# LTC3862-2.net
KiCad netlist of a schematic drawn in Altium Designer
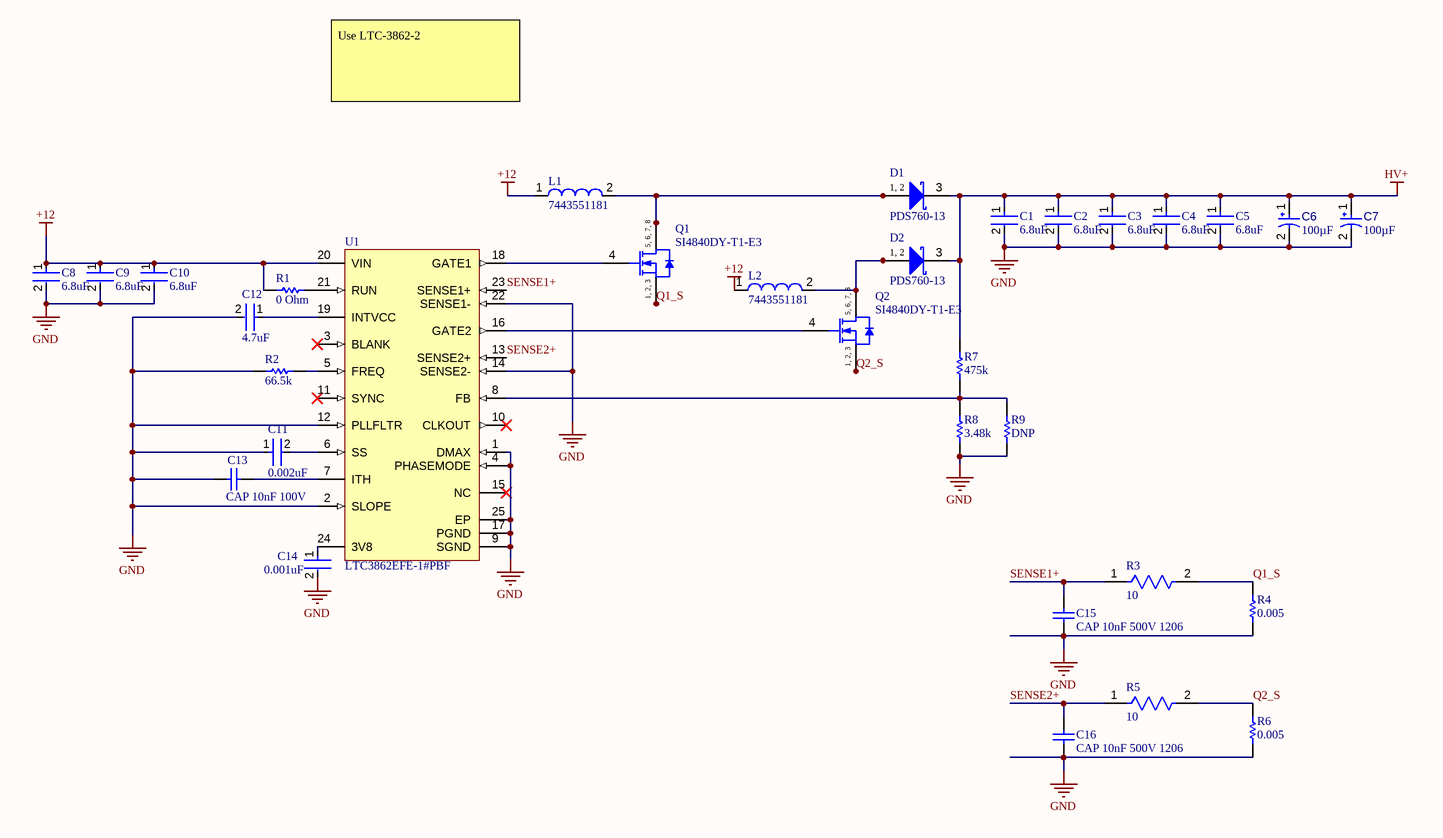
[diagram p0: LTC3862-2.SchDoc]

(export (version "E")
  (design (tool "Eeschema 10.0.6"))
  (components
    (comp (ref "C1")
      (value "6.8uF")
      (footprint "FP-C3216-160-0_2-MFG")
      (description "Multilayer Ceramic Capacitors 6.8uF ±20% 50V X5R SMD 1206\r\nC3216X5R1H685M160AB")
      (fields (field (name "TOLERANCE") "20%"))
      (libsource (lib "Altium Content Vault") (part "11868f565c42a9108669ba33697ecf6"))
    )
    (comp (ref "C2")
      (value "6.8uF")
      (footprint "FP-C3216-160-0_2-MFG")
      (description "Multilayer Ceramic Capacitors 6.8uF ±20% 50V X5R SMD 1206\r\nC3216X5R1H685M160AB")
      (fields (field (name "TOLERANCE") "20%"))
      (libsource (lib "Altium Content Vault") (part "11868f565c42a9108669ba33697ecf6"))
    )
    (comp (ref "C3")
      (value "6.8uF")
      (footprint "FP-C3216-160-0_2-MFG")
      (description "Multilayer Ceramic Capacitors 6.8uF ±20% 50V X5R SMD 1206\r\nC3216X5R1H685M160AB")
      (fields (field (name "TOLERANCE") "20%"))
      (libsource (lib "Altium Content Vault") (part "11868f565c42a9108669ba33697ecf6"))
    )
    (comp (ref "C4")
      (value "6.8uF")
      (footprint "FP-C3216-160-0_2-MFG")
      (description "Multilayer Ceramic Capacitors 6.8uF ±20% 50V X5R SMD 1206\r\nC3216X5R1H685M160AB")
      (fields (field (name "TOLERANCE") "20%"))
      (libsource (lib "Altium Content Vault") (part "11868f565c42a9108669ba33697ecf6"))
    )
    (comp (ref "C5")
      (value "6.8uF")
      (footprint "FP-C3216-160-0_2-MFG")
      (description "Multilayer Ceramic Capacitors 6.8uF ±20% 50V X5R SMD 1206\r\nC3216X5R1H685M160AB")
      (fields (field (name "TOLERANCE") "20%"))
      (libsource (lib "Altium Content Vault") (part "11868f565c42a9108669ba33697ecf6"))
    )
    (comp (ref "C6")
      (value "100µF")
      (footprint "CAPPR65-500-1600X1000X1700")
      (description "Aluminum Electrolytic Capacitor, 100 uF, +/- 20%, 200 V, -40 to 85 degC, 2-Pin THD, RoHS, Bulk")
      (fields (field (name "MANUFACTURER") "Panasonic") (field (name "TOLERANCE") "20%"))
      (libsource (lib "University of California Riverside - FSAE") (part "CAP-P-2"))
    )
    (comp (ref "C7")
      (value "100µF")
      (footprint "CAPPR65-500-1600X1000X1700")
      (description "Aluminum Electrolytic Capacitor, 100 uF, +/- 20%, 200 V, -40 to 85 degC, 2-Pin THD, RoHS, Bulk")
      (fields (field (name "MANUFACTURER") "Panasonic") (field (name "TOLERANCE") "20%"))
      (libsource (lib "University of California Riverside - FSAE") (part "CAP-P-2"))
    )
    (comp (ref "C8")
      (value "6.8uF")
      (footprint "FP-C3216-160-0_2-IPC_B")
      (description "Multilayer Ceramic Capacitors 6.8uF ±10% 25V X7R SMD 1206\r\nC3216X7R1E685K160AB")
      (fields (field (name "TOLERANCE") "10%"))
      (libsource (lib "Altium Content Vault") (part "11868f565c42a9108669ba33697ecf6"))
    )
    (comp (ref "C9")
      (value "6.8uF")
      (footprint "FP-C3216-160-0_2-IPC_B")
      (description "Multilayer Ceramic Capacitors 6.8uF ±10% 25V X7R SMD 1206\r\nC3216X7R1E685K160AB")
      (fields (field (name "TOLERANCE") "10%"))
      (libsource (lib "Altium Content Vault") (part "11868f565c42a9108669ba33697ecf6"))
    )
    (comp (ref "C10")
      (value "6.8uF")
      (footprint "FP-C3216-160-0_2-IPC_B")
      (description "Multilayer Ceramic Capacitors 6.8uF ±10% 25V X7R SMD 1206\r\nC3216X7R1E685K160AB")
      (fields (field (name "TOLERANCE") "10%"))
      (libsource (lib "Altium Content Vault") (part "11868f565c42a9108669ba33697ecf6"))
    )
    (comp (ref "C11")
      (value "0.002uF")
      (footprint "FP-C1206C-EB-MFG")
      (description "C1206 2,000 pF C0G 5.00% 100 V\r\nC1206C202J1GACTU")
      (fields (field (name "TOLERANCE") "0.05") (field (name "MANUFACTURER") "KEMET"))
      (libsource (lib "Altium Content Vault") (part "b4654b650e69147ec39a6b967a45e02"))
    )
    (comp (ref "C12")
      (value "4.7uF")
      (footprint "FP-GRM31C-0_2-e0_3_0_8-IPC_C")
      (description "Chip Multilayer Ceramic Capacitors for General Purpose, 1206, 4.7uF, X7R, 15%, 10%, 50V")
      (fields (field (name "VOLTAGE") "50V") (field (name "TOLERANCE") "10%"))
      (libsource (lib "Altium Content Vault") (part "02cd4be3c70576c341d710602a673aa"))
    )
    (comp (ref "C13")
      (value "CAP 10nF 100V")
      (footprint "CAPC1206(3216)170_N")
      (description "CAP 10nF 100V ±5% 1206 (3216 Metric) Thickness 1.7mm SMD")
      (fields (field (name "TOLERANCE") "Â±5%"))
      (libsource (lib "Altium Content Vault") (part "CAP"))
    )
    (comp (ref "C14")
      (value "0.001uF")
      (footprint "FP-C1206C-EB-MFG")
      (fields
        (field (name "MANUFACTURER PART NUMBER") "C1206C102J5GACTU")
        (field (name "TOLERANCE") "0.05")
        (field (name "MANUFACTURER") "KEMET")
      )
      (libsource (lib "Altium Content Vault") (part "b4654b650e69147ec39a6b967a45e02"))
    )
    (comp (ref "C15")
      (value "CAP 10nF 500V 1206")
      (footprint "CAPC1206(3216)170_N")
      (description "CAP 10nF 500V ±10% 1206 (3216 Metric) Thickness 1.7mm SMD")
      (fields (field (name "TOLERANCE") "Â±10%"))
      (libsource (lib "Altium Content Vault") (part "CAP"))
    )
    (comp (ref "C16")
      (value "CAP 10nF 500V 1206")
      (footprint "CAPC1206(3216)170_N")
      (description "CAP 10nF 500V ±10% 1206 (3216 Metric) Thickness 1.7mm SMD")
      (fields (field (name "TOLERANCE") "Â±10%"))
      (libsource (lib "Altium Content Vault") (part "CAP"))
    )
    (comp (ref "D1")
      (value "PDS760-13")
      (footprint "DIOD-POWERDI5-3_V")
      (description "Schottky Barrier Rectifier, 60 V, 7 A, -65 to 150 degC, 3-Pin SMD, RoHS, Tape and Reel")
      (fields (field (name "MANUFACTURER") "Diodes Inc"))
      (libsource (lib "Altium Content Vault") (part "DSKY-AAK-3_A"))
    )
    (comp (ref "D2")
      (value "PDS760-13")
      (footprint "DIOD-POWERDI5-3_V")
      (description "Schottky Barrier Rectifier, 60 V, 7 A, -65 to 150 degC, 3-Pin SMD, RoHS, Tape and Reel")
      (fields (field (name "MANUFACTURER") "Diodes Inc"))
      (libsource (lib "Altium Content Vault") (part "DSKY-AAK-3_A"))
    )
    (comp (ref "L1")
      (value "7443551181")
      (footprint "WE-HCI-1365")
      (description "SMD Flat Wire High Current Inductor WE-HCI, L=18.0 µH")
      (fields (field (name "MANUFACTURER") "Wuerth Elektronik"))
      (libsource (lib "Altium Content Vault") (part "PAS-IND-INDUCTOR-2"))
    )
    (comp (ref "L2")
      (value "7443551181")
      (footprint "WE-HCI-1365")
      (description "SMD Flat Wire High Current Inductor WE-HCI, L=18.0 µH")
      (fields (field (name "MANUFACTURER") "Wuerth Elektronik"))
      (libsource (lib "Altium Content Vault") (part "PAS-IND-INDUCTOR-2"))
    )
    (comp (ref "Q1")
      (value "SI4840DY-T1-E3")
      (footprint "VISH-SOIC-8_A_V")
      (description "N-Channel MOSFET, 40 V, -55 to 150 degC, 8-Pin SOIC, RoHS, Tape and Reel")
      (fields (field (name "MANUFACTURER") "Vishay"))
      (libsource (lib "Altium Content Vault") (part "NEMOS-SSSGDDDD-8"))
    )
    (comp (ref "Q2")
      (value "SI4840DY-T1-E3")
      (footprint "VISH-SOIC-8_A_V")
      (description "N-Channel MOSFET, 40 V, -55 to 150 degC, 8-Pin SOIC, RoHS, Tape and Reel")
      (fields (field (name "MANUFACTURER") "Vishay"))
      (libsource (lib "Altium Content Vault") (part "NEMOS-SSSGDDDD-8"))
    )
    (comp (ref "R1")
      (value "0 Ohm")
      (footprint "RESC3216X89X64LL25T25")
      (description "0 ohm 1206\r\nWSL120600000ZEA9")
      (fields (field (name "MANUFACTURER") "Vishay Dale") (field (name "PART NUMBER") "WSL120600000ZEA9"))
      (libsource (lib "Altium Content Vault") (part "RES"))
    )
    (comp (ref "R2")
      (value "66.5k")
      (footprint "RESC3216X70X50NL05T20")
      (description "ERJ-8ENF6652V")
      (fields (field (name "MANUFACTURER") "Panasonic"))
      (libsource (lib "Altium Content Vault") (part "RES"))
    )
    (comp (ref "R3")
      (value "10")
      (footprint "FP-CRCW1206-e3-IPC_A")
      (description "RES Thick Film, 10Ω, 1%, 0.25W, 100ppm/°C, 1206\r\nCRCW120610R0FKEA")
      (fields (field (name "TOLERANCE") "1%"))
      (libsource (lib "Altium Content Vault") (part "1029c3af85768c4190bb7ad29bc67b5"))
    )
    (comp (ref "R4")
      (value "0.005")
      (footprint "RESC3216X89X64LL25T25")
      (description "WSLP12065L000FEA")
      (fields (field (name "MANUFACTURER") "Vishay Dale"))
      (libsource (lib "Altium Content Vault") (part "RES"))
    )
    (comp (ref "R5")
      (value "10")
      (footprint "FP-CRCW1206-e3-IPC_A")
      (description "RES Thick Film, 10Ω, 1%, 0.25W, 100ppm/°C, 1206\r\nCRCW120610R0FKEA")
      (fields (field (name "TOLERANCE") "1%"))
      (libsource (lib "Altium Content Vault") (part "1029c3af85768c4190bb7ad29bc67b5"))
    )
    (comp (ref "R6")
      (value "0.005")
      (footprint "RESC3216X89X64LL25T25")
      (description "WSLP12065L000FEA")
      (fields (field (name "MANUFACTURER") "Vishay Dale"))
      (libsource (lib "Altium Content Vault") (part "RES"))
    )
    (comp (ref "R7")
      (value "475k")
      (footprint "RESC3216X60X45LL10T20")
      (description "CRCW1206475KFKEA")
      (fields (field (name "MANUFACTURER") "Vishay Dale"))
      (libsource (lib "Altium Content Vault") (part "RES"))
    )
    (comp (ref "R8")
      (value "3.48k")
      (footprint "RESC3216X70X50LL05T20")
      (description "ERJ-8ENF3481V")
      (fields (field (name "MANUFACTURER") "Panasonic"))
      (libsource (lib "Altium Content Vault") (part "RES"))
    )
    (comp (ref "R9")
      (value "DNP")
      (footprint "RESC3216X70X50LL05T20")
      (fields (field (name "MANUFACTURER") "Panasonic") (field (name "PART NUMBER") "ERJ-8ENF3481V"))
      (libsource (lib "Altium Content Vault") (part "RES"))
    )
    (comp (ref "U1")
      (value "LTC3862EFE-1#PBF")
      (footprint "LT-FE-24-EPV-AA_M")
      (fields (field (name "MANUFACTURER") "Linear Technology"))
      (libsource (lib "Altium Content Vault") (part "LT-LTC3862-X-FE-24"))
    )
  )
  (nets
    (net (code "1") (name "+12") (class "Default")
      (node (ref "C10") (pin "1") (pinfunction "1_1") (pintype "passive"))
      (node (ref "C8") (pin "1") (pinfunction "1_1") (pintype "passive"))
      (node (ref "C9") (pin "1") (pinfunction "1_1") (pintype "passive"))
      (node (ref "L1") (pin "1") (pinfunction "1_1") (pintype "passive"))
      (node (ref "L2") (pin "1") (pinfunction "1_1") (pintype "passive"))
      (node (ref "R1") (pin "1") (pinfunction "1_1") (pintype "passive"))
      (node (ref "U1") (pin "20") (pinfunction "VIN_20") (pintype "power_in"))
    )
    (net (code "2") (name "/Q1_S") (class "Default")
      (node (ref "Q1") (pin "1") (pinfunction "S_1") (pintype "passive"))
      (node (ref "Q1") (pin "2") (pinfunction "S_2") (pintype "passive"))
      (node (ref "Q1") (pin "3") (pinfunction "S_3") (pintype "passive"))
      (node (ref "R3") (pin "2") (pinfunction "2_2") (pintype "passive"))
      (node (ref "R4") (pin "2") (pinfunction "2_2") (pintype "passive"))
    )
    (net (code "3") (name "/Q2_S") (class "Default")
      (node (ref "Q2") (pin "1") (pinfunction "S_1") (pintype "passive"))
      (node (ref "Q2") (pin "2") (pinfunction "S_2") (pintype "passive"))
      (node (ref "Q2") (pin "3") (pinfunction "S_3") (pintype "passive"))
      (node (ref "R5") (pin "2") (pinfunction "2_2") (pintype "passive"))
      (node (ref "R6") (pin "2") (pinfunction "2_2") (pintype "passive"))
    )
    (net (code "4") (name "/SENSE1+") (class "Default")
      (node (ref "C15") (pin "1") (pinfunction "1_1") (pintype "passive"))
      (node (ref "R3") (pin "1") (pinfunction "1_1") (pintype "passive"))
      (node (ref "U1") (pin "23") (pinfunction "SENSE1+_23") (pintype "input"))
    )
    (net (code "5") (name "/SENSE2+") (class "Default")
      (node (ref "C16") (pin "1") (pinfunction "1_1") (pintype "passive"))
      (node (ref "R5") (pin "1") (pinfunction "1_1") (pintype "passive"))
      (node (ref "U1") (pin "13") (pinfunction "SENSE2+_13") (pintype "input"))
    )
    (net (code "6") (name "GND") (class "Default")
      (node (ref "C1") (pin "2") (pinfunction "2_2") (pintype "passive"))
      (node (ref "C10") (pin "2") (pinfunction "2_2") (pintype "passive"))
      (node (ref "C11") (pin "1") (pinfunction "1_1") (pintype "passive"))
      (node (ref "C12") (pin "2") (pinfunction "2_2") (pintype "passive"))
      (node (ref "C13") (pin "2") (pinfunction "2_2") (pintype "passive"))
      (node (ref "C14") (pin "2") (pinfunction "2_2") (pintype "passive"))
      (node (ref "C15") (pin "2") (pinfunction "2_2") (pintype "passive"))
      (node (ref "C16") (pin "2") (pinfunction "2_2") (pintype "passive"))
      (node (ref "C2") (pin "2") (pinfunction "2_2") (pintype "passive"))
      (node (ref "C3") (pin "2") (pinfunction "2_2") (pintype "passive"))
      (node (ref "C4") (pin "2") (pinfunction "2_2") (pintype "passive"))
      (node (ref "C5") (pin "2") (pinfunction "2_2") (pintype "passive"))
      (node (ref "C6") (pin "2") (pinfunction "2_2") (pintype "passive"))
      (node (ref "C7") (pin "2") (pinfunction "2_2") (pintype "passive"))
      (node (ref "C8") (pin "2") (pinfunction "2_2") (pintype "passive"))
      (node (ref "C9") (pin "2") (pinfunction "2_2") (pintype "passive"))
      (node (ref "R2") (pin "1") (pinfunction "1_1") (pintype "passive"))
      (node (ref "R4") (pin "1") (pinfunction "1_1") (pintype "passive"))
      (node (ref "R6") (pin "1") (pinfunction "1_1") (pintype "passive"))
      (node (ref "R8") (pin "1") (pinfunction "1_1") (pintype "passive"))
      (node (ref "R9") (pin "1") (pinfunction "1_1") (pintype "passive"))
      (node (ref "U1") (pin "1") (pinfunction "DMAX_1") (pintype "input"))
      (node (ref "U1") (pin "12") (pinfunction "PLLFLTR_12") (pintype "input"))
      (node (ref "U1") (pin "14") (pinfunction "SENSE2-_14") (pintype "input"))
      (node (ref "U1") (pin "17") (pinfunction "PGND_17") (pintype "power_in"))
      (node (ref "U1") (pin "2") (pinfunction "SLOPE_2") (pintype "input"))
      (node (ref "U1") (pin "22") (pinfunction "SENSE1-_22") (pintype "input"))
      (node (ref "U1") (pin "25") (pinfunction "EP_25") (pintype "power_in"))
      (node (ref "U1") (pin "4") (pinfunction "PHASEMODE_4") (pintype "input"))
      (node (ref "U1") (pin "9") (pinfunction "SGND_9") (pintype "power_in"))
    )
    (net (code "7") (name "HV+") (class "Default")
      (node (ref "C1") (pin "1") (pinfunction "1_1") (pintype "passive"))
      (node (ref "C2") (pin "1") (pinfunction "1_1") (pintype "passive"))
      (node (ref "C3") (pin "1") (pinfunction "1_1") (pintype "passive"))
      (node (ref "C4") (pin "1") (pinfunction "1_1") (pintype "passive"))
      (node (ref "C5") (pin "1") (pinfunction "1_1") (pintype "passive"))
      (node (ref "C6") (pin "1") (pinfunction "1_1") (pintype "passive"))
      (node (ref "C7") (pin "1") (pinfunction "1_1") (pintype "passive"))
      (node (ref "D1") (pin "3") (pinfunction "K_3") (pintype "passive"))
      (node (ref "D2") (pin "3") (pinfunction "K_3") (pintype "passive"))
      (node (ref "R7") (pin "2") (pinfunction "2_2") (pintype "passive"))
    )
    (net (code "8") (name "Net-(D1-A-Pad1)") (class "Default")
      (node (ref "D1") (pin "1") (pinfunction "A_1") (pintype "passive"))
      (node (ref "D1") (pin "2") (pinfunction "A_2") (pintype "passive"))
      (node (ref "L1") (pin "2") (pinfunction "2_2") (pintype "passive"))
      (node (ref "Q1") (pin "5") (pinfunction "D_5") (pintype "passive"))
      (node (ref "Q1") (pin "6") (pinfunction "D_6") (pintype "passive"))
      (node (ref "Q1") (pin "7") (pinfunction "D_7") (pintype "passive"))
      (node (ref "Q1") (pin "8") (pinfunction "D_8") (pintype "passive"))
    )
    (net (code "9") (name "Net-(D2-A-Pad1)") (class "Default")
      (node (ref "D2") (pin "1") (pinfunction "A_1") (pintype "passive"))
      (node (ref "D2") (pin "2") (pinfunction "A_2") (pintype "passive"))
      (node (ref "L2") (pin "2") (pinfunction "2_2") (pintype "passive"))
      (node (ref "Q2") (pin "5") (pinfunction "D_5") (pintype "passive"))
      (node (ref "Q2") (pin "6") (pinfunction "D_6") (pintype "passive"))
      (node (ref "Q2") (pin "7") (pinfunction "D_7") (pintype "passive"))
      (node (ref "Q2") (pin "8") (pinfunction "D_8") (pintype "passive"))
    )
    (net (code "10") (name "Net-(Q1-G)") (class "Default")
      (node (ref "Q1") (pin "4") (pinfunction "G_4") (pintype "passive"))
      (node (ref "U1") (pin "18") (pinfunction "GATE1_18") (pintype "output"))
    )
    (net (code "11") (name "Net-(Q2-G)") (class "Default")
      (node (ref "Q2") (pin "4") (pinfunction "G_4") (pintype "passive"))
      (node (ref "U1") (pin "16") (pinfunction "GATE2_16") (pintype "output"))
    )
    (net (code "12") (name "Net-(U1-3V8)") (class "Default")
      (node (ref "C14") (pin "1") (pinfunction "1_1") (pintype "passive"))
      (node (ref "U1") (pin "24") (pinfunction "3V8_24") (pintype "power_in"))
    )
    (net (code "13") (name "Net-(U1-FB)") (class "Default")
      (node (ref "R7") (pin "1") (pinfunction "1_1") (pintype "passive"))
      (node (ref "R8") (pin "2") (pinfunction "2_2") (pintype "passive"))
      (node (ref "R9") (pin "2") (pinfunction "2_2") (pintype "passive"))
      (node (ref "U1") (pin "8") (pinfunction "FB_8") (pintype "input"))
    )
    (net (code "14") (name "Net-(U1-FREQ)") (class "Default")
      (node (ref "R2") (pin "2") (pinfunction "2_2") (pintype "passive"))
      (node (ref "U1") (pin "5") (pinfunction "FREQ_5") (pintype "input"))
    )
    (net (code "15") (name "Net-(U1-INTVCC)") (class "Default")
      (node (ref "C12") (pin "1") (pinfunction "1_1") (pintype "passive"))
      (node (ref "U1") (pin "19") (pinfunction "INTVCC_19") (pintype "power_in"))
    )
    (net (code "16") (name "Net-(U1-ITH)") (class "Default")
      (node (ref "C13") (pin "1") (pinfunction "1_1") (pintype "passive"))
      (node (ref "U1") (pin "7") (pinfunction "ITH_7") (pintype "passive"))
    )
    (net (code "17") (name "Net-(U1-RUN)") (class "Default")
      (node (ref "R1") (pin "2") (pinfunction "2_2") (pintype "passive"))
      (node (ref "U1") (pin "21") (pinfunction "RUN_21") (pintype "input"))
    )
    (net (code "18") (name "Net-(U1-SS)") (class "Default")
      (node (ref "C11") (pin "2") (pinfunction "2_2") (pintype "passive"))
      (node (ref "U1") (pin "6") (pinfunction "SS_6") (pintype "input"))
    )
    (net (code "19") (name "unconnected-(U1-BLANK-Pad3)") (class "Default")
      (node (ref "U1") (pin "3") (pinfunction "BLANK_3") (pintype "input+no_connect"))
    )
    (net (code "20") (name "unconnected-(U1-CLKOUT-Pad10)") (class "Default")
      (node (ref "U1") (pin "10") (pinfunction "CLKOUT_10") (pintype "output+no_connect"))
    )
    (net (code "21") (name "unconnected-(U1-NC-Pad15)") (class "Default")
      (node (ref "U1") (pin "15") (pinfunction "NC_15") (pintype "passive+no_connect"))
    )
    (net (code "22") (name "unconnected-(U1-SYNC-Pad11)") (class "Default")
      (node (ref "U1") (pin "11") (pinfunction "SYNC_11") (pintype "input+no_connect"))
    )
  )
)
